# switch.net
KiCad netlist of a schematic drawn in EAGLE
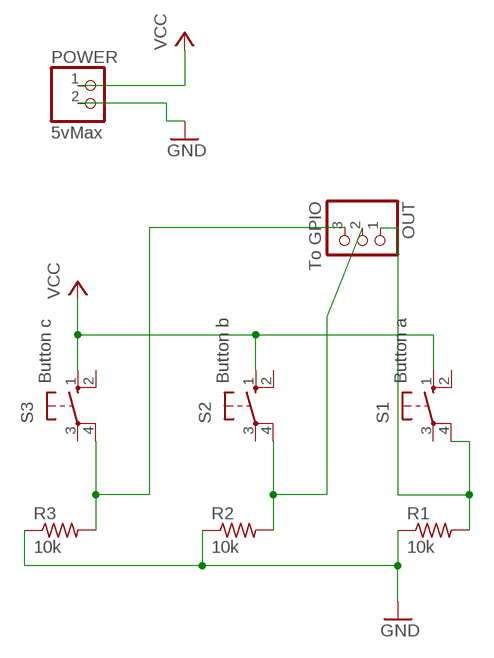
[diagram p0: schematic, sheet 1]

(export (version "E")
  (design (tool "Eeschema 10.0.6"))
  (components
    (comp (ref "OUT")
      (value "To GPIO")
      (footprint "eagle-import:1X03")
      (libsource (lib "eagle-import") (part "PINHD-1X3"))
    )
    (comp (ref "POWER")
      (value "5vMax")
      (footprint "eagle-import:1X02")
      (libsource (lib "eagle-import") (part "PINHD-1X2"))
    )
    (comp (ref "R1")
      (value "10k")
      (footprint "eagle-import:0204_7")
      (libsource (lib "eagle-import") (part "R-US_0204/7"))
    )
    (comp (ref "R2")
      (value "10k")
      (footprint "eagle-import:0204_7")
      (libsource (lib "eagle-import") (part "R-US_0204/7"))
    )
    (comp (ref "R3")
      (value "10k")
      (footprint "eagle-import:0204_7")
      (libsource (lib "eagle-import") (part "R-US_0204/7"))
    )
    (comp (ref "S1")
      (value "Button a")
      (footprint "eagle-import:B3F-10XX")
      (fields (field (name "MPN") "B3F-1000"))
      (libsource (lib "eagle-import") (part "10-XX"))
    )
    (comp (ref "S2")
      (value "Button b")
      (footprint "eagle-import:B3F-10XX")
      (fields (field (name "MPN") "B3F-1000"))
      (libsource (lib "eagle-import") (part "10-XX"))
    )
    (comp (ref "S3")
      (value "Button c")
      (footprint "eagle-import:B3F-10XX")
      (fields (field (name "MPN") "B3F-1000"))
      (libsource (lib "eagle-import") (part "10-XX"))
    )
  )
  (nets
    (net (code "1") (name "GND") (class "Default")
      (node (ref "POWER") (pin "2") (pinfunction "2_2") (pintype "passive"))
      (node (ref "R1") (pin "1") (pinfunction "1_1") (pintype "passive"))
      (node (ref "R2") (pin "1") (pinfunction "1_1") (pintype "passive"))
      (node (ref "R3") (pin "1") (pinfunction "1_1") (pintype "passive"))
    )
    (net (code "2") (name "Net-(S1-P1)") (class "Default")
      (node (ref "OUT") (pin "1") (pinfunction "1_1") (pintype "passive"))
      (node (ref "R1") (pin "2") (pinfunction "2_2") (pintype "passive"))
      (node (ref "S1") (pin "4") (pinfunction "P1_4") (pintype "passive"))
    )
    (net (code "3") (name "Net-(S2-P1)") (class "Default")
      (node (ref "OUT") (pin "2") (pinfunction "2_2") (pintype "passive"))
      (node (ref "R2") (pin "2") (pinfunction "2_2") (pintype "passive"))
      (node (ref "S2") (pin "4") (pinfunction "P1_4") (pintype "passive"))
    )
    (net (code "4") (name "Net-(S3-P1)") (class "Default")
      (node (ref "OUT") (pin "3") (pinfunction "3_3") (pintype "passive"))
      (node (ref "R3") (pin "2") (pinfunction "2_2") (pintype "passive"))
      (node (ref "S3") (pin "4") (pinfunction "P1_4") (pintype "passive"))
    )
    (net (code "5") (name "VCC") (class "Default")
      (node (ref "POWER") (pin "1") (pinfunction "1_1") (pintype "passive"))
      (node (ref "S1") (pin "1") (pinfunction "S_1") (pintype "passive"))
      (node (ref "S2") (pin "1") (pinfunction "S_1") (pintype "passive"))
      (node (ref "S3") (pin "1") (pinfunction "S_1") (pintype "passive"))
    )
    (net (code "6") (name "unconnected-(S1-P-Pad3)") (class "Default")
      (node (ref "S1") (pin "3") (pinfunction "P_3") (pintype "passive"))
    )
    (net (code "7") (name "unconnected-(S1-S1-Pad2)") (class "Default")
      (node (ref "S1") (pin "2") (pinfunction "S1_2") (pintype "passive"))
    )
    (net (code "8") (name "unconnected-(S2-P-Pad3)") (class "Default")
      (node (ref "S2") (pin "3") (pinfunction "P_3") (pintype "passive"))
    )
    (net (code "9") (name "unconnected-(S2-S1-Pad2)") (class "Default")
      (node (ref "S2") (pin "2") (pinfunction "S1_2") (pintype "passive"))
    )
    (net (code "10") (name "unconnected-(S3-P-Pad3)") (class "Default")
      (node (ref "S3") (pin "3") (pinfunction "P_3") (pintype "passive"))
    )
    (net (code "11") (name "unconnected-(S3-S1-Pad2)") (class "Default")
      (node (ref "S3") (pin "2") (pinfunction "S1_2") (pintype "passive"))
    )
  )
)
